# TransmitterSchematicP.net
KiCad netlist of a schematic drawn in EAGLE
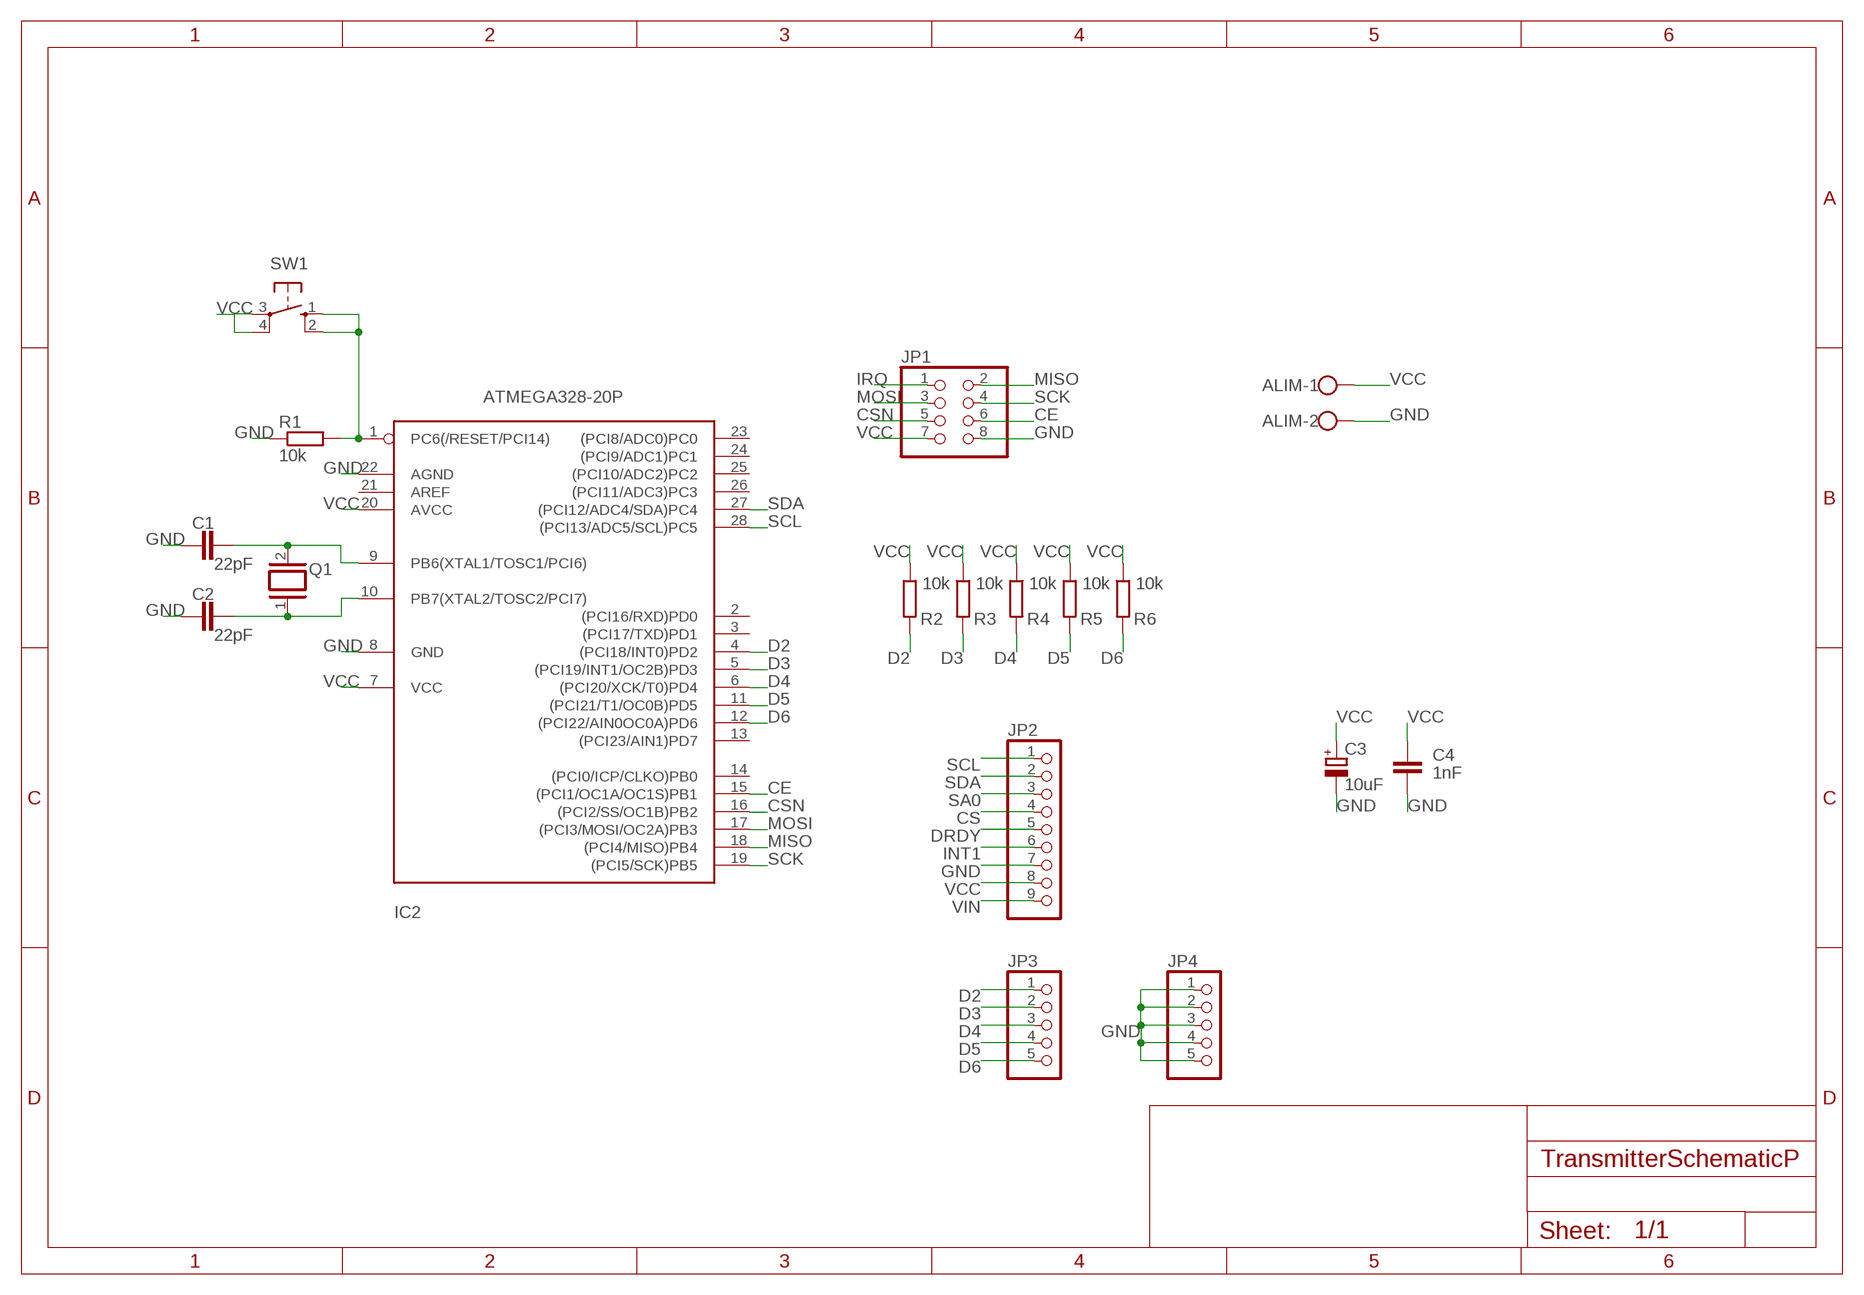
[diagram p0: schematic, sheet 1]

(export (version "E")
  (design (tool "Eeschema 10.0.6"))
  (components
    (comp (ref "ALIM")
      (value "W237-102")
      (footprint "eagle-import:W237-102")
      (fields (field (name "MPN") "237-102"))
      (libsource (lib "eagle-import") (part "W237-102"))
    )
    (comp (ref "C1")
      (value "22pF")
      (footprint "eagle-import:C050-024X044")
      (libsource (lib "eagle-import") (part "C-EU050-024X044"))
    )
    (comp (ref "C2")
      (value "22pF")
      (footprint "eagle-import:C050-024X044")
      (libsource (lib "eagle-import") (part "C-EU050-024X044"))
    )
    (comp (ref "C3")
      (value "10uF")
      (footprint "eagle-import:E2,5-5")
      (libsource (lib "eagle-import") (part "CPOL-EUE2.5-5"))
    )
    (comp (ref "C4")
      (value "1nF")
      (footprint "eagle-import:C050-024X044")
      (libsource (lib "eagle-import") (part "C-EU050-024X044"))
    )
    (comp (ref "IC2")
      (value "ATMEGA328-20P")
      (footprint "eagle-import:DIL28-3")
      (libsource (lib "eagle-import") (part "ATMEGA328P-20"))
    )
    (comp (ref "JP1")
      (value "PINHD-2X4")
      (footprint "eagle-import:2X04")
      (libsource (lib "eagle-import") (part "PINHD-2X4"))
    )
    (comp (ref "JP2")
      (value "PINHD-1X9")
      (footprint "eagle-import:1X09")
      (libsource (lib "eagle-import") (part "PINHD-1X9"))
    )
    (comp (ref "JP3")
      (value "PINHD-1X5")
      (footprint "eagle-import:1X05")
      (libsource (lib "eagle-import") (part "PINHD-1X5"))
    )
    (comp (ref "JP4")
      (value "PINHD-1X5")
      (footprint "eagle-import:1X05")
      (libsource (lib "eagle-import") (part "PINHD-1X5"))
    )
    (comp (ref "Q1")
      (value "XTAL/S")
      (footprint "eagle-import:QS")
      (libsource (lib "eagle-import") (part "XTAL/S"))
    )
    (comp (ref "R1")
      (value "10k")
      (footprint "eagle-import:0204_7")
      (libsource (lib "eagle-import") (part "R-EU_0204/7"))
    )
    (comp (ref "R2")
      (value "10k")
      (footprint "eagle-import:0204_7")
      (libsource (lib "eagle-import") (part "R-EU_0204/7"))
    )
    (comp (ref "R3")
      (value "10k")
      (footprint "eagle-import:0204_7")
      (libsource (lib "eagle-import") (part "R-EU_0204/7"))
    )
    (comp (ref "R4")
      (value "10k")
      (footprint "eagle-import:0204_7")
      (libsource (lib "eagle-import") (part "R-EU_0204/7"))
    )
    (comp (ref "R5")
      (value "10k")
      (footprint "eagle-import:0204_7")
      (libsource (lib "eagle-import") (part "R-EU_0204/7"))
    )
    (comp (ref "R6")
      (value "10k")
      (footprint "eagle-import:0204_7")
      (libsource (lib "eagle-import") (part "R-EU_0204/7"))
    )
    (comp (ref "SW1")
      (value "10-XX")
      (footprint "eagle-import:B3F-10XX")
      (libsource (lib "eagle-import") (part "10-XX"))
    )
  )
  (nets
    (net (code "1") (name "/CE") (class "Default")
      (node (ref "IC2") (pin "15") (pinfunction "(PCI1/OC1A/OC1S)PB1_15") (pintype "bidirectional"))
      (node (ref "JP1") (pin "6") (pinfunction "6_6") (pintype "passive"))
    )
    (net (code "2") (name "/CS") (class "Default")
      (node (ref "JP2") (pin "4") (pinfunction "4_4") (pintype "passive"))
    )
    (net (code "3") (name "/CSN") (class "Default")
      (node (ref "IC2") (pin "16") (pinfunction "(PCI2/SS/OC1B)PB2_16") (pintype "bidirectional"))
      (node (ref "JP1") (pin "5") (pinfunction "5_5") (pintype "passive"))
    )
    (net (code "4") (name "/D2") (class "Default")
      (node (ref "IC2") (pin "4") (pinfunction "(PCI18/INT0)PD2_4") (pintype "bidirectional"))
      (node (ref "JP3") (pin "1") (pinfunction "1_1") (pintype "passive"))
      (node (ref "R2") (pin "2") (pinfunction "2_2") (pintype "passive"))
    )
    (net (code "5") (name "/D3") (class "Default")
      (node (ref "IC2") (pin "5") (pinfunction "(PCI19/INT1/OC2B)PD3_5") (pintype "bidirectional"))
      (node (ref "JP3") (pin "2") (pinfunction "2_2") (pintype "passive"))
      (node (ref "R3") (pin "2") (pinfunction "2_2") (pintype "passive"))
    )
    (net (code "6") (name "/D4") (class "Default")
      (node (ref "IC2") (pin "6") (pinfunction "(PCI20/XCK/T0)PD4_6") (pintype "bidirectional"))
      (node (ref "JP3") (pin "3") (pinfunction "3_3") (pintype "passive"))
      (node (ref "R4") (pin "2") (pinfunction "2_2") (pintype "passive"))
    )
    (net (code "7") (name "/D5") (class "Default")
      (node (ref "IC2") (pin "11") (pinfunction "(PCI21/T1/OC0B)PD5_11") (pintype "bidirectional"))
      (node (ref "JP3") (pin "4") (pinfunction "4_4") (pintype "passive"))
      (node (ref "R5") (pin "2") (pinfunction "2_2") (pintype "passive"))
    )
    (net (code "8") (name "/D6") (class "Default")
      (node (ref "IC2") (pin "12") (pinfunction "(PCI22/AIN0OC0A)PD6_12") (pintype "bidirectional"))
      (node (ref "JP3") (pin "5") (pinfunction "5_5") (pintype "passive"))
      (node (ref "R6") (pin "2") (pinfunction "2_2") (pintype "passive"))
    )
    (net (code "9") (name "/DRDY") (class "Default")
      (node (ref "JP2") (pin "5") (pinfunction "5_5") (pintype "passive"))
    )
    (net (code "10") (name "/GND") (class "Default")
      (node (ref "ALIM") (pin "2") (pinfunction "KL_2") (pintype "passive"))
      (node (ref "C1") (pin "1") (pinfunction "1_1") (pintype "passive"))
      (node (ref "C2") (pin "1") (pinfunction "1_1") (pintype "passive"))
      (node (ref "C3") (pin "-") (pinfunction "-_-") (pintype "passive"))
      (node (ref "C4") (pin "1") (pinfunction "1_1") (pintype "passive"))
      (node (ref "IC2") (pin "22") (pinfunction "AGND_22") (pintype "bidirectional"))
      (node (ref "IC2") (pin "8") (pinfunction "GND_8") (pintype "bidirectional"))
      (node (ref "JP1") (pin "8") (pinfunction "8_8") (pintype "passive"))
      (node (ref "JP2") (pin "7") (pinfunction "7_7") (pintype "passive"))
      (node (ref "JP4") (pin "1") (pinfunction "1_1") (pintype "passive"))
      (node (ref "JP4") (pin "2") (pinfunction "2_2") (pintype "passive"))
      (node (ref "JP4") (pin "3") (pinfunction "3_3") (pintype "passive"))
      (node (ref "JP4") (pin "4") (pinfunction "4_4") (pintype "passive"))
      (node (ref "JP4") (pin "5") (pinfunction "5_5") (pintype "passive"))
      (node (ref "R1") (pin "1") (pinfunction "1_1") (pintype "passive"))
    )
    (net (code "11") (name "/INT1") (class "Default")
      (node (ref "JP2") (pin "6") (pinfunction "6_6") (pintype "passive"))
    )
    (net (code "12") (name "/IRQ") (class "Default")
      (node (ref "JP1") (pin "1") (pinfunction "1_1") (pintype "passive"))
    )
    (net (code "13") (name "/MISO") (class "Default")
      (node (ref "IC2") (pin "18") (pinfunction "(PCI4/MISO)PB4_18") (pintype "bidirectional"))
      (node (ref "JP1") (pin "2") (pinfunction "2_2") (pintype "passive"))
    )
    (net (code "14") (name "/MOSI") (class "Default")
      (node (ref "IC2") (pin "17") (pinfunction "(PCI3/MOSI/OC2A)PB3_17") (pintype "bidirectional"))
      (node (ref "JP1") (pin "3") (pinfunction "3_3") (pintype "passive"))
    )
    (net (code "15") (name "/SA0") (class "Default")
      (node (ref "JP2") (pin "3") (pinfunction "3_3") (pintype "passive"))
    )
    (net (code "16") (name "/SCK") (class "Default")
      (node (ref "IC2") (pin "19") (pinfunction "(PCI5/SCK)PB5_19") (pintype "bidirectional"))
      (node (ref "JP1") (pin "4") (pinfunction "4_4") (pintype "passive"))
    )
    (net (code "17") (name "/SCL") (class "Default")
      (node (ref "IC2") (pin "28") (pinfunction "(PCI13/ADC5/SCL)PC5_28") (pintype "bidirectional"))
      (node (ref "JP2") (pin "1") (pinfunction "1_1") (pintype "passive"))
    )
    (net (code "18") (name "/SDA") (class "Default")
      (node (ref "IC2") (pin "27") (pinfunction "(PCI12/ADC4/SDA)PC4_27") (pintype "bidirectional"))
      (node (ref "JP2") (pin "2") (pinfunction "2_2") (pintype "passive"))
    )
    (net (code "19") (name "/VCC") (class "Default")
      (node (ref "ALIM") (pin "1") (pinfunction "KL_1") (pintype "passive"))
      (node (ref "C3") (pin "+") (pinfunction "+_+") (pintype "passive"))
      (node (ref "C4") (pin "2") (pinfunction "2_2") (pintype "passive"))
      (node (ref "IC2") (pin "20") (pinfunction "AVCC_20") (pintype "bidirectional"))
      (node (ref "IC2") (pin "7") (pinfunction "VCC_7") (pintype "bidirectional"))
      (node (ref "JP1") (pin "7") (pinfunction "7_7") (pintype "passive"))
      (node (ref "JP2") (pin "8") (pinfunction "8_8") (pintype "passive"))
      (node (ref "R2") (pin "1") (pinfunction "1_1") (pintype "passive"))
      (node (ref "R3") (pin "1") (pinfunction "1_1") (pintype "passive"))
      (node (ref "R4") (pin "1") (pinfunction "1_1") (pintype "passive"))
      (node (ref "R5") (pin "1") (pinfunction "1_1") (pintype "passive"))
      (node (ref "R6") (pin "1") (pinfunction "1_1") (pintype "passive"))
      (node (ref "SW1") (pin "3") (pinfunction "P_3") (pintype "passive"))
      (node (ref "SW1") (pin "4") (pinfunction "P1_4") (pintype "passive"))
    )
    (net (code "20") (name "/VIN") (class "Default")
      (node (ref "JP2") (pin "9") (pinfunction "9_9") (pintype "passive"))
    )
    (net (code "21") (name "Net-(IC2-PB6(XTAL1{slash}TOSC1{slash}PCI6))") (class "Default")
      (node (ref "C1") (pin "2") (pinfunction "2_2") (pintype "passive"))
      (node (ref "IC2") (pin "9") (pinfunction "PB6(XTAL1/TOSC1/PCI6)_9") (pintype "bidirectional"))
      (node (ref "Q1") (pin "2") (pinfunction "2_2") (pintype "passive"))
    )
    (net (code "22") (name "Net-(IC2-PB7(XTAL2{slash}TOSC2{slash}PCI7))") (class "Default")
      (node (ref "C2") (pin "2") (pinfunction "2_2") (pintype "passive"))
      (node (ref "IC2") (pin "10") (pinfunction "PB7(XTAL2/TOSC2/PCI7)_10") (pintype "bidirectional"))
      (node (ref "Q1") (pin "1") (pinfunction "1_1") (pintype "passive"))
    )
    (net (code "23") (name "Net-(IC2-PC6({slash}RESET{slash}PCI14))") (class "Default")
      (node (ref "IC2") (pin "1") (pinfunction "PC6(/RESET/PCI14)_1") (pintype "bidirectional"))
      (node (ref "R1") (pin "2") (pinfunction "2_2") (pintype "passive"))
      (node (ref "SW1") (pin "1") (pinfunction "S_1") (pintype "passive"))
      (node (ref "SW1") (pin "2") (pinfunction "S1_2") (pintype "passive"))
    )
    (net (code "24") (name "unconnected-(IC2-(PCI0{slash}ICP{slash}CLKO)PB0-Pad14)") (class "Default")
      (node (ref "IC2") (pin "14") (pinfunction "(PCI0/ICP/CLKO)PB0_14") (pintype "bidirectional"))
    )
    (net (code "25") (name "unconnected-(IC2-(PCI8{slash}ADC0)PC0-Pad23)") (class "Default")
      (node (ref "IC2") (pin "23") (pinfunction "(PCI8/ADC0)PC0_23") (pintype "bidirectional"))
    )
    (net (code "26") (name "unconnected-(IC2-(PCI9{slash}ADC1)PC1-Pad24)") (class "Default")
      (node (ref "IC2") (pin "24") (pinfunction "(PCI9/ADC1)PC1_24") (pintype "bidirectional"))
    )
    (net (code "27") (name "unconnected-(IC2-(PCI10{slash}ADC2)PC2-Pad25)") (class "Default")
      (node (ref "IC2") (pin "25") (pinfunction "(PCI10/ADC2)PC2_25") (pintype "bidirectional"))
    )
    (net (code "28") (name "unconnected-(IC2-(PCI11{slash}ADC3)PC3-Pad26)") (class "Default")
      (node (ref "IC2") (pin "26") (pinfunction "(PCI11/ADC3)PC3_26") (pintype "bidirectional"))
    )
    (net (code "29") (name "unconnected-(IC2-(PCI16{slash}RXD)PD0-Pad2)") (class "Default")
      (node (ref "IC2") (pin "2") (pinfunction "(PCI16/RXD)PD0_2") (pintype "bidirectional"))
    )
    (net (code "30") (name "unconnected-(IC2-(PCI17{slash}TXD)PD1-Pad3)") (class "Default")
      (node (ref "IC2") (pin "3") (pinfunction "(PCI17/TXD)PD1_3") (pintype "bidirectional"))
    )
    (net (code "31") (name "unconnected-(IC2-(PCI23{slash}AIN1)PD7-Pad13)") (class "Default")
      (node (ref "IC2") (pin "13") (pinfunction "(PCI23/AIN1)PD7_13") (pintype "bidirectional"))
    )
    (net (code "32") (name "unconnected-(IC2-AREF-Pad21)") (class "Default")
      (node (ref "IC2") (pin "21") (pinfunction "AREF_21") (pintype "bidirectional"))
    )
  )
)
